# RTC_IMU.net
KiCad netlist of a schematic drawn in Altium Designer
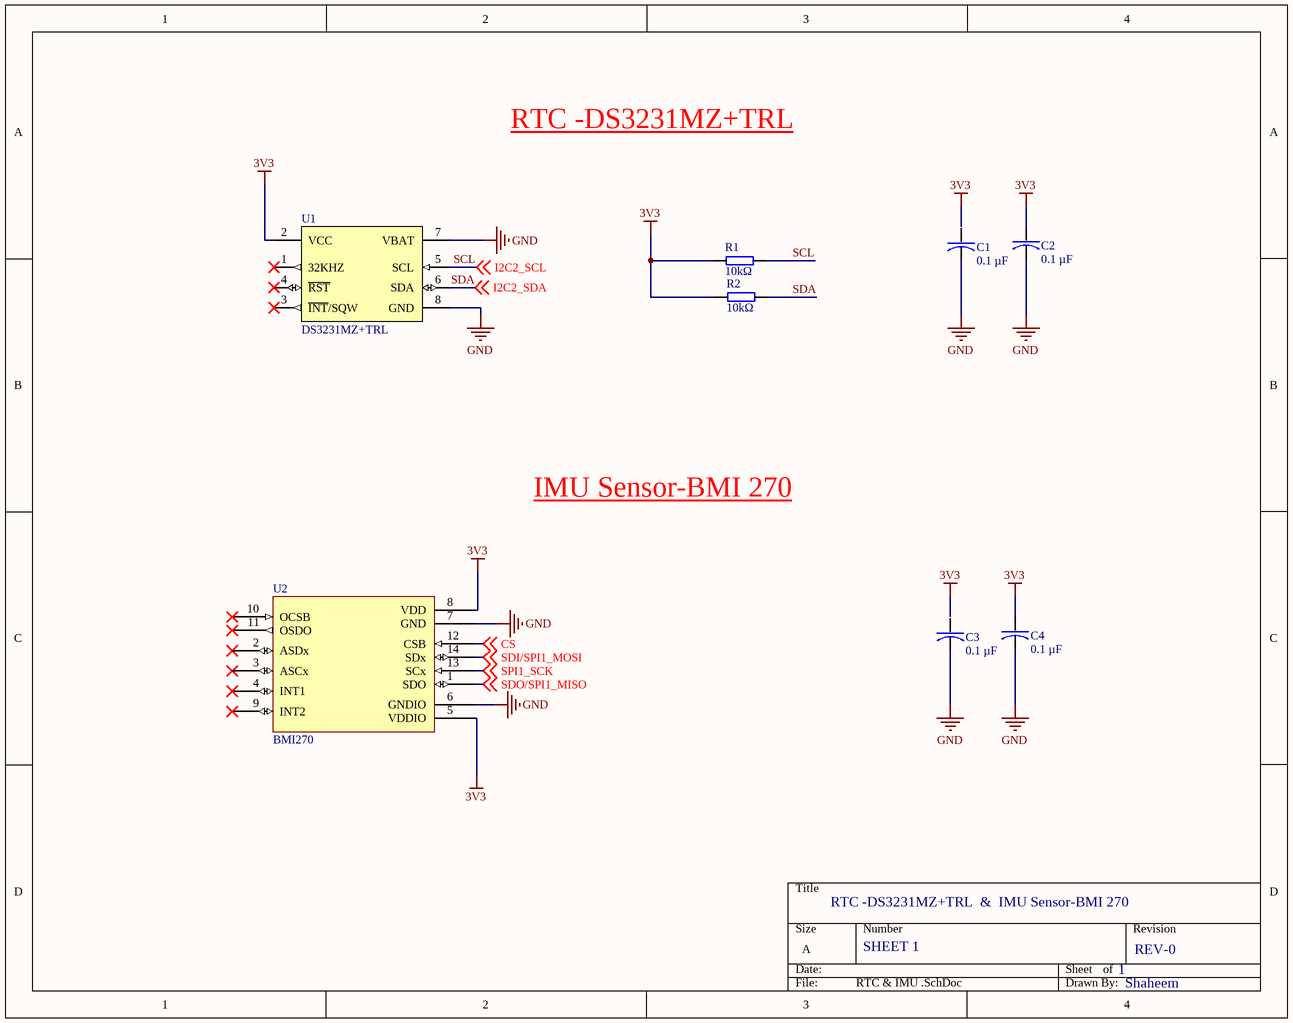
[diagram p0: RTC & IMU .SchDoc]

(export (version "E")
  (design (tool "Eeschema 10.0.6"))
  (components
    (comp (ref "C1")
      (value "0.1 µF")
      (footprint "GRM155R71H104KE14-0.1uf ceramic capacitor")
      (description "0402 0.1 uF 25 V ±10% Tolerance X7R SMT Multilayer Ceramic Capacitor")
      (fields
        (field (name "MANUFACTURER") "Murata")
        (field (name "MANUFACTURER PART NUMBER") "GRM155R71E104KE14J")
      )
      (libsource (lib "Component_3") (part "GRM155R71E104KE14J- 0.1 µF"))
    )
    (comp (ref "C2")
      (value "0.1 µF")
      (footprint "GRM155R71H104KE14-0.1uf ceramic capacitor")
      (description "0402 0.1 uF 25 V ±10% Tolerance X7R SMT Multilayer Ceramic Capacitor")
      (fields
        (field (name "MANUFACTURER") "Murata")
        (field (name "MANUFACTURER PART NUMBER") "GRM155R71E104KE14J")
      )
      (libsource (lib "Component_3") (part "GRM155R71E104KE14J- 0.1 µF"))
    )
    (comp (ref "C3")
      (value "0.1 µF")
      (footprint "GRM155R71H104KE14-0.1uf ceramic capacitor")
      (description "0402 0.1 uF 25 V ±10% Tolerance X7R SMT Multilayer Ceramic Capacitor")
      (fields
        (field (name "MANUFACTURER") "Murata")
        (field (name "MANUFACTURER PART NUMBER") "GRM155R71E104KE14J")
      )
      (libsource (lib "Component_3") (part "GRM155R71E104KE14J- 0.1 µF"))
    )
    (comp (ref "C4")
      (value "0.1 µF")
      (footprint "GRM155R71H104KE14-0.1uf ceramic capacitor")
      (description "0402 0.1 uF 25 V ±10% Tolerance X7R SMT Multilayer Ceramic Capacitor")
      (fields
        (field (name "MANUFACTURER") "Murata")
        (field (name "MANUFACTURER PART NUMBER") "GRM155R71E104KE14J")
      )
      (libsource (lib "Component_3") (part "GRM155R71E104KE14J- 0.1 µF"))
    )
    (comp (ref "R1")
      (value "10kΩ")
      (footprint "RC0603FR-0710KL-10kohm Thick film.")
      (description "100mW Thick Film Resistors ±100ppm/℃ ±1% 10kΩ 0603 Chip Resistor - Surface Mount ROHS")
      (fields
        (field (name "MANUFACTURER") "Yageo Group")
        (field (name "MANUFACTURER PART NUMBER") "RC0603FR-0710KL")
      )
      (libsource (lib "Component_3") (part "RC0603FR-0710KL-10kohm Thick film"))
    )
    (comp (ref "R2")
      (value "10kΩ")
      (footprint "RC0603FR-0710KL-10kohm Thick film.")
      (description "100mW Thick Film Resistors ±100ppm/℃ ±1% 10kΩ 0603 Chip Resistor - Surface Mount ROHS")
      (fields
        (field (name "MANUFACTURER") "Yageo Group")
        (field (name "MANUFACTURER PART NUMBER") "RC0603FR-0710KL")
      )
      (libsource (lib "Component_3") (part "RC0603FR-0710KL-10kohm Thick film"))
    )
    (comp (ref "U1")
      (value "DS3231MZ+TRL")
      (footprint "DS3231MZ+TRL")
      (description "HH: MM: SS (12/24 hr) 128bit 2.3V 5.5V 2, I2C, Serial YY-MM-DD-dd SOIC-8 4.9mm*3.9mm*1.55mm")
      (fields (field (name "MANUFACTURER") "Analog Devices"))
      (libsource (lib "Component_1") (part "DS3231MZ+TRL"))
    )
    (comp (ref "U2")
      (value "BMI270")
      (footprint "BMI270")
      (description "LGA-14(2.5x3) Attitude Sensor/Gyroscope ROHS")
      (fields (field (name "MANUFACTURER") "Bosch Tools"))
      (libsource (lib "Component_3") (part "BMI270"))
    )
  )
  (nets
    (net (code "1") (name "3V3") (class "Default")
      (node (ref "C2") (pin "2") (pinfunction "2_2") (pintype "passive"))
      (node (ref "C4") (pin "2") (pinfunction "2_2") (pintype "passive"))
      (node (ref "R1") (pin "2") (pinfunction "2_2") (pintype "passive"))
      (node (ref "R2") (pin "2") (pinfunction "2_2") (pintype "passive"))
      (node (ref "U1") (pin "2") (pinfunction "VCC_2") (pintype "power_in"))
      (node (ref "U2") (pin "5") (pinfunction "VDDIO_5") (pintype "power_in"))
      (node (ref "U2") (pin "8") (pinfunction "VDD_8") (pintype "power_in"))
    )
    (net (code "2") (name "CS") (class "Default")
      (node (ref "U2") (pin "12") (pinfunction "CSB_12") (pintype "input"))
    )
    (net (code "3") (name "GND") (class "Default")
      (node (ref "C1") (pin "1") (pinfunction "1_1") (pintype "passive"))
      (node (ref "C2") (pin "1") (pinfunction "1_1") (pintype "passive"))
      (node (ref "C3") (pin "1") (pinfunction "1_1") (pintype "passive"))
      (node (ref "C4") (pin "1") (pinfunction "1_1") (pintype "passive"))
      (node (ref "U1") (pin "7") (pinfunction "VBAT_7") (pintype "power_in"))
      (node (ref "U1") (pin "8") (pinfunction "GND_8") (pintype "power_in"))
      (node (ref "U2") (pin "6") (pinfunction "GNDIO_6") (pintype "passive"))
      (node (ref "U2") (pin "7") (pinfunction "GND_7") (pintype "passive"))
    )
    (net (code "4") (name "I2C2_SCL") (class "Default")
      (node (ref "R1") (pin "1") (pinfunction "1_1") (pintype "passive"))
      (node (ref "U1") (pin "5") (pinfunction "SCL_5") (pintype "input"))
    )
    (net (code "5") (name "I2C2_SDA") (class "Default")
      (node (ref "R2") (pin "1") (pinfunction "1_1") (pintype "passive"))
      (node (ref "U1") (pin "6") (pinfunction "SDA_6") (pintype "bidirectional"))
    )
    (net (code "6") (name "SDI{slash}SPI1_MOSI") (class "Default")
      (node (ref "U2") (pin "14") (pinfunction "SDx_14") (pintype "bidirectional"))
    )
    (net (code "7") (name "SDO{slash}SPI1_MISO") (class "Default")
      (node (ref "U2") (pin "1") (pinfunction "SDO_1") (pintype "bidirectional"))
    )
    (net (code "8") (name "SPI1_SCK") (class "Default")
      (node (ref "U2") (pin "13") (pinfunction "SCx_13") (pintype "input"))
    )
    (net (code "9") (name "unconnected-(C1-Pad2)") (class "Default")
      (node (ref "C1") (pin "2") (pinfunction "2_2") (pintype "passive"))
    )
    (net (code "10") (name "unconnected-(C3-Pad2)") (class "Default")
      (node (ref "C3") (pin "2") (pinfunction "2_2") (pintype "passive"))
    )
    (net (code "11") (name "unconnected-(U1-32KHZ-Pad1)") (class "Default")
      (node (ref "U1") (pin "1") (pinfunction "32KHZ_1") (pintype "output+no_connect"))
    )
    (net (code "12") (name "unconnected-(U1-~{INT}{slash}SQW-Pad3)") (class "Default")
      (node (ref "U1") (pin "3") (pinfunction "~{INT}/SQW_3") (pintype "output+no_connect"))
    )
    (net (code "13") (name "unconnected-(U1-~{RST}-Pad4)") (class "Default")
      (node (ref "U1") (pin "4") (pinfunction "~{RST}_4") (pintype "bidirectional+no_connect"))
    )
    (net (code "14") (name "unconnected-(U2-ASCx-Pad3)") (class "Default")
      (node (ref "U2") (pin "3") (pinfunction "ASCx_3") (pintype "bidirectional+no_connect"))
    )
    (net (code "15") (name "unconnected-(U2-ASDx-Pad2)") (class "Default")
      (node (ref "U2") (pin "2") (pinfunction "ASDx_2") (pintype "bidirectional+no_connect"))
    )
    (net (code "16") (name "unconnected-(U2-INT1-Pad4)") (class "Default")
      (node (ref "U2") (pin "4") (pinfunction "INT1_4") (pintype "bidirectional+no_connect"))
    )
    (net (code "17") (name "unconnected-(U2-INT2-Pad9)") (class "Default")
      (node (ref "U2") (pin "9") (pinfunction "INT2_9") (pintype "bidirectional+no_connect"))
    )
    (net (code "18") (name "unconnected-(U2-OCSB-Pad10)") (class "Default")
      (node (ref "U2") (pin "10") (pinfunction "OCSB_10") (pintype "input+no_connect"))
    )
    (net (code "19") (name "unconnected-(U2-OSDO-Pad11)") (class "Default")
      (node (ref "U2") (pin "11") (pinfunction "OSDO_11") (pintype "output+no_connect"))
    )
  )
)
